# LoRa_RN5.net
KiCad netlist of a schematic drawn in EAGLE
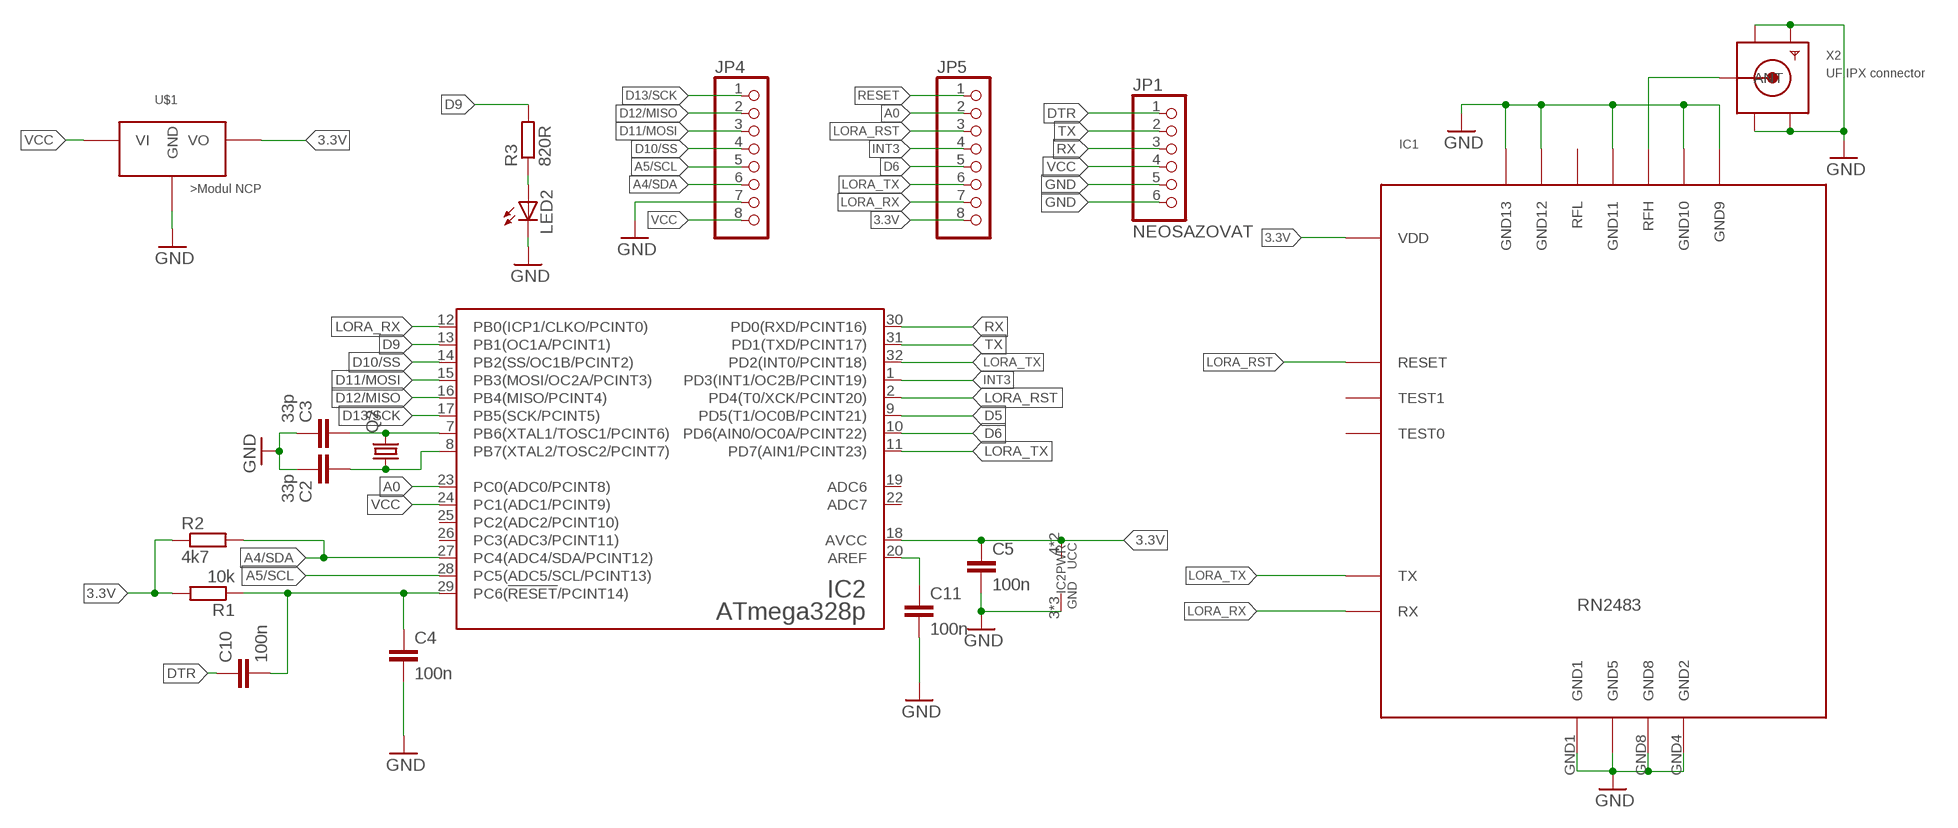
[diagram p0: schematic, sheet 1]

(export (version "E")
  (design (tool "Eeschema 10.0.6"))
  (components
    (comp (ref "C2")
      (value "33p")
      (footprint "eagle-import:C0805")
      (libsource (lib "eagle-import") (part "C-EUC0805"))
    )
    (comp (ref "C3")
      (value "33p")
      (footprint "eagle-import:C0805")
      (libsource (lib "eagle-import") (part "C-EUC0805"))
    )
    (comp (ref "C4")
      (value "100n")
      (footprint "eagle-import:C0805")
      (libsource (lib "eagle-import") (part "C-EUC0805"))
    )
    (comp (ref "C5")
      (value "100n")
      (footprint "eagle-import:C0805")
      (libsource (lib "eagle-import") (part "C-EUC0805"))
    )
    (comp (ref "C10")
      (value "100n")
      (footprint "eagle-import:C0805")
      (libsource (lib "eagle-import") (part "C-EUC0805"))
    )
    (comp (ref "C11")
      (value "100n")
      (footprint "eagle-import:C0805")
      (libsource (lib "eagle-import") (part "C-EUC0805"))
    )
    (comp (ref "IC1")
      (value "RN2483_MIN")
      (footprint "eagle-import:RN2483_2")
      (libsource (lib "eagle-import") (part "RN2483_MIN"))
    )
    (comp (ref "IC2")
      (value "ATmega328p")
      (footprint "eagle-import:TQFP32-08")
      (libsource (lib "eagle-import") (part "ATMEGA48/88/168/328-AU"))
    )
    (comp (ref "JP1")
      (value "NEOSAZOVAT")
      (footprint "eagle-import:1X06")
      (libsource (lib "eagle-import") (part "PINHD-1X6"))
    )
    (comp (ref "JP4")
      (value "PINHD-1X8")
      (footprint "eagle-import:1X08")
      (libsource (lib "eagle-import") (part "PINHD-1X8"))
    )
    (comp (ref "JP5")
      (value "PINHD-1X8")
      (footprint "eagle-import:1X08")
      (libsource (lib "eagle-import") (part "PINHD-1X8"))
    )
    (comp (ref "LED2")
      (value "LEDCHIPLED_1206")
      (footprint "eagle-import:CHIPLED_1206")
      (libsource (lib "eagle-import") (part "LEDCHIPLED_1206"))
    )
    (comp (ref "Q2")
      (value "CRYSTALCTS406")
      (footprint "eagle-import:CTS406")
      (libsource (lib "eagle-import") (part "CRYSTALCTS406"))
    )
    (comp (ref "R1")
      (value "10k")
      (footprint "eagle-import:R0805")
      (libsource (lib "eagle-import") (part "R-EU_R0805"))
    )
    (comp (ref "R2")
      (value "4k7")
      (footprint "eagle-import:R0805")
      (libsource (lib "eagle-import") (part "R-EU_R0805"))
    )
    (comp (ref "R3")
      (value "820R")
      (footprint "eagle-import:R0805")
      (libsource (lib "eagle-import") (part "R-EU_R0805"))
    )
    (comp (ref "U$1")
      (value "NEOSAZOVAT")
      (footprint "eagle-import:MOD_NCP1402")
      (libsource (lib "eagle-import") (part "MOD_NCP1402"))
    )
    (comp (ref "X2")
      (value "UF.IPX connector")
      (footprint "eagle-import:SMA_EDGELAUNCH_UFL")
      (libsource (lib "eagle-import") (part "SMACONNECTOR_EDGE_UFL"))
    )
  )
  (nets
    (net (code "1") (name "3.3V") (class "Default")
      (node (ref "C5") (pin "1") (pinfunction "1_1") (pintype "passive"))
      (node (ref "IC1") (pin "VDD") (pinfunction "VDD_VDD") (pintype "bidirectional"))
      (node (ref "IC2") (pin "18") (pinfunction "AVCC_18") (pintype "power_in"))
      (node (ref "IC2") (pin "4") (pinfunction "UCC_4") (pintype "power_in"))
      (node (ref "IC2") (pin "6") (pinfunction "UCC_6") (pintype "power_in"))
      (node (ref "JP5") (pin "8") (pinfunction "8_8") (pintype "passive"))
      (node (ref "R1") (pin "2") (pinfunction "2_2") (pintype "passive"))
      (node (ref "R2") (pin "1") (pinfunction "1_1") (pintype "passive"))
      (node (ref "U$1") (pin "VO") (pinfunction "VO_VO") (pintype "bidirectional"))
    )
    (net (code "2") (name "A0") (class "Default")
      (node (ref "IC2") (pin "23") (pinfunction "PC0(ADC0/PCINT8)_23") (pintype "bidirectional"))
      (node (ref "JP5") (pin "2") (pinfunction "2_2") (pintype "passive"))
    )
    (net (code "3") (name "A4{slash}SDA") (class "Default")
      (node (ref "IC2") (pin "27") (pinfunction "PC4(ADC4/SDA/PCINT12)_27") (pintype "bidirectional"))
      (node (ref "JP4") (pin "6") (pinfunction "6_6") (pintype "passive"))
      (node (ref "R2") (pin "2") (pinfunction "2_2") (pintype "passive"))
    )
    (net (code "4") (name "A5{slash}SCL") (class "Default")
      (node (ref "IC2") (pin "28") (pinfunction "PC5(ADC5/SCL/PCINT13)_28") (pintype "bidirectional"))
      (node (ref "JP4") (pin "5") (pinfunction "5_5") (pintype "passive"))
    )
    (net (code "5") (name "D5") (class "Default")
      (node (ref "IC2") (pin "9") (pinfunction "PD5(T1/OC0B/PCINT21)_9") (pintype "bidirectional"))
    )
    (net (code "6") (name "D6") (class "Default")
      (node (ref "IC2") (pin "10") (pinfunction "PD6(AIN0/OC0A/PCINT22)_10") (pintype "bidirectional"))
      (node (ref "JP5") (pin "5") (pinfunction "5_5") (pintype "passive"))
    )
    (net (code "7") (name "D9") (class "Default")
      (node (ref "IC2") (pin "13") (pinfunction "PB1(OC1A/PCINT1)_13") (pintype "bidirectional"))
      (node (ref "R3") (pin "2") (pinfunction "2_2") (pintype "passive"))
    )
    (net (code "8") (name "D10{slash}SS") (class "Default")
      (node (ref "IC2") (pin "14") (pinfunction "PB2(SS/OC1B/PCINT2)_14") (pintype "bidirectional"))
      (node (ref "JP4") (pin "4") (pinfunction "4_4") (pintype "passive"))
    )
    (net (code "9") (name "D11{slash}MOSI") (class "Default")
      (node (ref "IC2") (pin "15") (pinfunction "PB3(MOSI/OC2A/PCINT3)_15") (pintype "bidirectional"))
      (node (ref "JP4") (pin "3") (pinfunction "3_3") (pintype "passive"))
    )
    (net (code "10") (name "D12{slash}MISO") (class "Default")
      (node (ref "IC2") (pin "16") (pinfunction "PB4(MISO/PCINT4)_16") (pintype "bidirectional"))
      (node (ref "JP4") (pin "2") (pinfunction "2_2") (pintype "passive"))
    )
    (net (code "11") (name "D13{slash}SCK") (class "Default")
      (node (ref "IC2") (pin "17") (pinfunction "PB5(SCK/PCINT5)_17") (pintype "bidirectional"))
      (node (ref "JP4") (pin "1") (pinfunction "1_1") (pintype "passive"))
    )
    (net (code "12") (name "DTR") (class "Default")
      (node (ref "C10") (pin "1") (pinfunction "1_1") (pintype "passive"))
      (node (ref "JP1") (pin "1") (pinfunction "1_1") (pintype "passive"))
    )
    (net (code "13") (name "GND") (class "Default")
      (node (ref "C11") (pin "2") (pinfunction "2_2") (pintype "passive"))
      (node (ref "C2") (pin "1") (pinfunction "1_1") (pintype "passive"))
      (node (ref "C3") (pin "1") (pinfunction "1_1") (pintype "passive"))
      (node (ref "C4") (pin "2") (pinfunction "2_2") (pintype "passive"))
      (node (ref "C5") (pin "2") (pinfunction "2_2") (pintype "passive"))
      (node (ref "IC1") (pin "GND1") (pinfunction "GND1_GND1") (pintype "bidirectional"))
      (node (ref "IC1") (pin "GND10") (pinfunction "GND10_GND10") (pintype "bidirectional"))
      (node (ref "IC1") (pin "GND11") (pinfunction "GND11_GND11") (pintype "bidirectional"))
      (node (ref "IC1") (pin "GND12") (pinfunction "GND12_GND12") (pintype "bidirectional"))
      (node (ref "IC1") (pin "GND13") (pinfunction "GND13_GND13") (pintype "bidirectional"))
      (node (ref "IC1") (pin "GND4") (pinfunction "GND2_GND4") (pintype "bidirectional"))
      (node (ref "IC1") (pin "GND5") (pinfunction "GND5_GND5") (pintype "bidirectional"))
      (node (ref "IC1") (pin "GND8") (pinfunction "GND8_GND8") (pintype "bidirectional"))
      (node (ref "IC1") (pin "GND9") (pinfunction "GND9_GND9") (pintype "bidirectional"))
      (node (ref "IC2") (pin "21") (pinfunction "GND_21") (pintype "power_in"))
      (node (ref "IC2") (pin "3") (pinfunction "GND_3") (pintype "power_in"))
      (node (ref "IC2") (pin "5") (pinfunction "GND_5") (pintype "power_in"))
      (node (ref "JP1") (pin "5") (pinfunction "5_5") (pintype "passive"))
      (node (ref "JP1") (pin "6") (pinfunction "6_6") (pintype "passive"))
      (node (ref "JP4") (pin "7") (pinfunction "7_7") (pintype "passive"))
      (node (ref "LED2") (pin "C") (pinfunction "C_C") (pintype "passive"))
      (node (ref "U$1") (pin "GND") (pinfunction "GND_GND") (pintype "bidirectional"))
      (node (ref "X2") (pin "GND@1") (pinfunction "GND1_GND@1") (pintype "power_in"))
      (node (ref "X2") (pin "GND@2") (pinfunction "GND2_GND@2") (pintype "power_in"))
      (node (ref "X2") (pin "GND@3") (pinfunction "GND3_GND@3") (pintype "power_in"))
      (node (ref "X2") (pin "GND@4") (pinfunction "GND4_GND@4") (pintype "power_in"))
    )
    (net (code "14") (name "INT3") (class "Default")
      (node (ref "IC2") (pin "1") (pinfunction "PD3(INT1/OC2B/PCINT19)_1") (pintype "bidirectional"))
      (node (ref "JP5") (pin "4") (pinfunction "4_4") (pintype "passive"))
    )
    (net (code "15") (name "LORA_RST") (class "Default")
      (node (ref "IC1") (pin "RESET") (pinfunction "RESET_RESET") (pintype "bidirectional"))
      (node (ref "IC2") (pin "2") (pinfunction "PD4(T0/XCK/PCINT20)_2") (pintype "bidirectional"))
      (node (ref "JP5") (pin "3") (pinfunction "3_3") (pintype "passive"))
    )
    (net (code "16") (name "LORA_RX") (class "Default")
      (node (ref "IC1") (pin "RX") (pinfunction "RX_RX") (pintype "bidirectional"))
      (node (ref "IC2") (pin "12") (pinfunction "PB0(ICP1/CLKO/PCINT0)_12") (pintype "bidirectional"))
      (node (ref "JP5") (pin "7") (pinfunction "7_7") (pintype "passive"))
    )
    (net (code "17") (name "LORA_TX") (class "Default")
      (node (ref "IC1") (pin "TX") (pinfunction "TX_TX") (pintype "bidirectional"))
      (node (ref "IC2") (pin "11") (pinfunction "PD7(AIN1/PCINT23)_11") (pintype "bidirectional"))
      (node (ref "IC2") (pin "32") (pinfunction "PD2(INT0/PCINT18)_32") (pintype "bidirectional"))
      (node (ref "JP5") (pin "6") (pinfunction "6_6") (pintype "passive"))
    )
    (net (code "18") (name "Net-(IC2A-AREF)") (class "Default")
      (node (ref "C11") (pin "1") (pinfunction "1_1") (pintype "passive"))
      (node (ref "IC2") (pin "20") (pinfunction "AREF_20") (pintype "passive"))
    )
    (net (code "19") (name "Net-(IC2A-PB6(XTAL1{slash}TOSC1{slash}PCINT6))") (class "Default")
      (node (ref "C3") (pin "2") (pinfunction "2_2") (pintype "passive"))
      (node (ref "IC2") (pin "7") (pinfunction "PB6(XTAL1/TOSC1/PCINT6)_7") (pintype "bidirectional"))
      (node (ref "Q2") (pin "3") (pinfunction "2_3") (pintype "passive"))
    )
    (net (code "20") (name "Net-(IC2A-PB7(XTAL2{slash}TOSC2{slash}PCINT7))") (class "Default")
      (node (ref "C2") (pin "2") (pinfunction "2_2") (pintype "passive"))
      (node (ref "IC2") (pin "8") (pinfunction "PB7(XTAL2/TOSC2/PCINT7)_8") (pintype "bidirectional"))
      (node (ref "Q2") (pin "1") (pinfunction "1_1") (pintype "passive"))
    )
    (net (code "21") (name "Net-(LED2-PadA)") (class "Default")
      (node (ref "LED2") (pin "A") (pinfunction "A_A") (pintype "passive"))
      (node (ref "R3") (pin "1") (pinfunction "1_1") (pintype "passive"))
    )
    (net (code "22") (name "Net-(X2-ANT)") (class "Default")
      (node (ref "IC1") (pin "RFH") (pinfunction "RFH_RFH") (pintype "bidirectional"))
      (node (ref "X2") (pin "P") (pinfunction "ANT_P") (pintype "bidirectional"))
    )
    (net (code "23") (name "RESET") (class "Default")
      (node (ref "C10") (pin "2") (pinfunction "2_2") (pintype "passive"))
      (node (ref "C4") (pin "1") (pinfunction "1_1") (pintype "passive"))
      (node (ref "IC2") (pin "29") (pinfunction "PC6(~{RESET}/PCINT14)_29") (pintype "bidirectional"))
      (node (ref "JP5") (pin "1") (pinfunction "1_1") (pintype "passive"))
      (node (ref "R1") (pin "1") (pinfunction "1_1") (pintype "passive"))
    )
    (net (code "24") (name "RX") (class "Default")
      (node (ref "IC2") (pin "30") (pinfunction "PD0(RXD/PCINT16)_30") (pintype "bidirectional"))
      (node (ref "JP1") (pin "3") (pinfunction "3_3") (pintype "passive"))
    )
    (net (code "25") (name "TX") (class "Default")
      (node (ref "IC2") (pin "31") (pinfunction "PD1(TXD/PCINT17)_31") (pintype "bidirectional"))
      (node (ref "JP1") (pin "2") (pinfunction "2_2") (pintype "passive"))
    )
    (net (code "26") (name "VCC") (class "Default")
      (node (ref "IC2") (pin "24") (pinfunction "PC1(ADC1/PCINT9)_24") (pintype "bidirectional"))
      (node (ref "JP1") (pin "4") (pinfunction "4_4") (pintype "passive"))
      (node (ref "JP4") (pin "8") (pinfunction "8_8") (pintype "passive"))
      (node (ref "U$1") (pin "VI") (pinfunction "VI_VI") (pintype "bidirectional"))
    )
    (net (code "27") (name "unconnected-(IC1-PadRFL)") (class "Default")
      (node (ref "IC1") (pin "RFL") (pinfunction "RFL_RFL") (pintype "bidirectional"))
    )
    (net (code "28") (name "unconnected-(IC1-PadTEST0)") (class "Default")
      (node (ref "IC1") (pin "TEST0") (pinfunction "TEST0_TEST0") (pintype "bidirectional"))
    )
    (net (code "29") (name "unconnected-(IC1-PadTEST1)") (class "Default")
      (node (ref "IC1") (pin "TEST1") (pinfunction "TEST1_TEST1") (pintype "bidirectional"))
    )
    (net (code "30") (name "unconnected-(IC2A-ADC6-Pad19)") (class "Default")
      (node (ref "IC2") (pin "19") (pinfunction "ADC6_19") (pintype "passive"))
    )
    (net (code "31") (name "unconnected-(IC2A-ADC7-Pad22)") (class "Default")
      (node (ref "IC2") (pin "22") (pinfunction "ADC7_22") (pintype "passive"))
    )
    (net (code "32") (name "unconnected-(IC2A-PC2(ADC2{slash}PCINT10)-Pad25)") (class "Default")
      (node (ref "IC2") (pin "25") (pinfunction "PC2(ADC2/PCINT10)_25") (pintype "bidirectional"))
    )
    (net (code "33") (name "unconnected-(IC2A-PC3(ADC3{slash}PCINT11)-Pad26)") (class "Default")
      (node (ref "IC2") (pin "26") (pinfunction "PC3(ADC3/PCINT11)_26") (pintype "bidirectional"))
    )
  )
)
